# LabPower-FB_V2.net
KiCad netlist of a schematic drawn in EAGLE
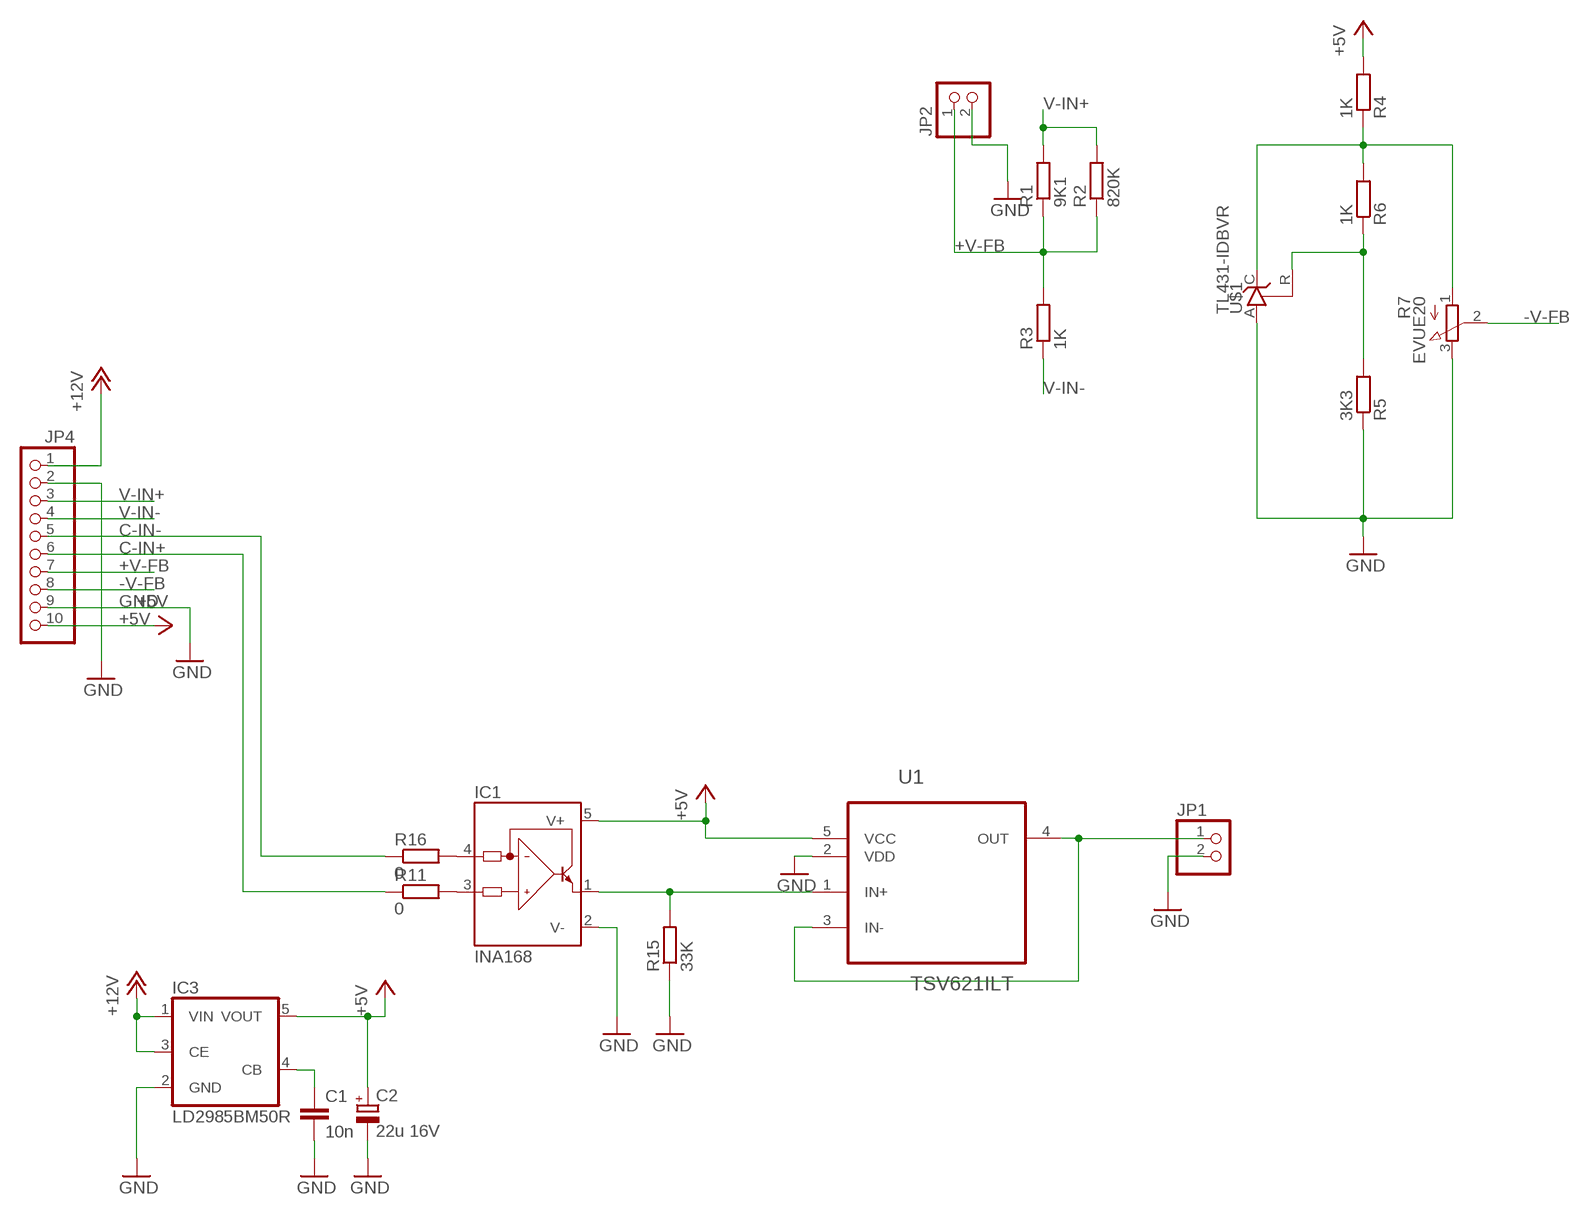
[diagram p0: schematic, sheet 1]

(export (version "E")
  (design (tool "Eeschema 10.0.6"))
  (components
    (comp (ref "C1")
      (value "10n")
      (footprint "eagle-import:C0805")
      (libsource (lib "eagle-import") (part "C-EUC0805"))
    )
    (comp (ref "C2")
      (value "22u 16V")
      (footprint "eagle-import:B_3528-21W")
      (libsource (lib "eagle-import") (part "CPOL-EUB/3528-21W"))
    )
    (comp (ref "IC1")
      (value "INA168")
      (footprint "eagle-import:SOT23-5")
      (fields (field (name "MF") "TEXAS INSTRUMENTS") (field (name "MPN") "INA168NA/250"))
      (libsource (lib "eagle-import") (part "INA168"))
    )
    (comp (ref "IC3")
      (value "LD2985BM50R")
      (footprint "eagle-import:SOT25")
      (libsource (lib "eagle-import") (part "TS5205"))
    )
    (comp (ref "JP1")
      (value "PINHD-1X2/90")
      (footprint "eagle-import:1X02_90")
      (libsource (lib "eagle-import") (part "PINHD-1X2/90"))
    )
    (comp (ref "JP2")
      (value "PINHD-1X2/90")
      (footprint "eagle-import:1X02_90")
      (libsource (lib "eagle-import") (part "PINHD-1X2/90"))
    )
    (comp (ref "JP4")
      (value "PINHD-1X10")
      (footprint "eagle-import:1X10")
      (libsource (lib "eagle-import") (part "PINHD-1X10"))
    )
    (comp (ref "R1")
      (value "9K1")
      (footprint "eagle-import:R0805")
      (libsource (lib "eagle-import") (part "R-EU_R0805"))
    )
    (comp (ref "R2")
      (value "820K")
      (footprint "eagle-import:R0805")
      (libsource (lib "eagle-import") (part "R-EU_R0805"))
    )
    (comp (ref "R3")
      (value "1K")
      (footprint "eagle-import:R0805")
      (libsource (lib "eagle-import") (part "R-EU_R0805"))
    )
    (comp (ref "R4")
      (value "1K")
      (footprint "eagle-import:R0805")
      (libsource (lib "eagle-import") (part "R-EU_R0805"))
    )
    (comp (ref "R5")
      (value "3K3")
      (footprint "eagle-import:R0805")
      (libsource (lib "eagle-import") (part "R-EU_R0805"))
    )
    (comp (ref "R6")
      (value "1K")
      (footprint "eagle-import:R0805")
      (libsource (lib "eagle-import") (part "R-EU_R0805"))
    )
    (comp (ref "R7")
      (value "EVUE20")
      (footprint "eagle-import:EVUE")
      (libsource (lib "eagle-import") (part "EVUE20"))
    )
    (comp (ref "R11")
      (value "0")
      (footprint "eagle-import:R0805")
      (libsource (lib "eagle-import") (part "R-EU_R0805"))
    )
    (comp (ref "R15")
      (value "33K")
      (footprint "eagle-import:R0805")
      (libsource (lib "eagle-import") (part "R-EU_R0805"))
    )
    (comp (ref "R16")
      (value "0")
      (footprint "eagle-import:R0805")
      (libsource (lib "eagle-import") (part "R-EU_R0805"))
    )
    (comp (ref "U$1")
      (value "TL431-IDBVR")
      (footprint "eagle-import:SOT23-5")
      (libsource (lib "eagle-import") (part "TL431-IDBVR"))
    )
    (comp (ref "U1")
      (value "TSV621ILT")
      (footprint "eagle-import:SOT95P280X145-5N")
      (libsource (lib "eagle-import") (part "TSV621ILT"))
    )
  )
  (nets
    (net (code "1") (name "+5V") (class "Default")
      (node (ref "C2") (pin "+") (pinfunction "+_+") (pintype "passive"))
      (node (ref "IC1") (pin "5") (pinfunction "V+_5") (pintype "power_in"))
      (node (ref "IC3") (pin "5") (pinfunction "VOUT_5") (pintype "passive"))
      (node (ref "JP4") (pin "10") (pinfunction "10_10") (pintype "passive"))
      (node (ref "R4") (pin "2") (pinfunction "2_2") (pintype "passive"))
      (node (ref "U1") (pin "5") (pinfunction "VCC_5") (pintype "power_in"))
    )
    (net (code "2") (name "+12V") (class "Default")
      (node (ref "IC3") (pin "1") (pinfunction "VIN_1") (pintype "input"))
      (node (ref "IC3") (pin "3") (pinfunction "CE_3") (pintype "input"))
      (node (ref "JP4") (pin "1") (pinfunction "1_1") (pintype "passive"))
    )
    (net (code "3") (name "/+V-FB") (class "Default")
      (node (ref "JP2") (pin "1") (pinfunction "1_1") (pintype "passive"))
      (node (ref "JP4") (pin "7") (pinfunction "7_7") (pintype "passive"))
      (node (ref "R1") (pin "1") (pinfunction "1_1") (pintype "passive"))
      (node (ref "R2") (pin "1") (pinfunction "1_1") (pintype "passive"))
      (node (ref "R3") (pin "2") (pinfunction "2_2") (pintype "passive"))
    )
    (net (code "4") (name "/-V-FB") (class "Default")
      (node (ref "JP4") (pin "8") (pinfunction "8_8") (pintype "passive"))
      (node (ref "R7") (pin "2") (pinfunction "S_2") (pintype "passive"))
    )
    (net (code "5") (name "/C-IN+") (class "Default")
      (node (ref "JP4") (pin "6") (pinfunction "6_6") (pintype "passive"))
      (node (ref "R11") (pin "1") (pinfunction "1_1") (pintype "passive"))
    )
    (net (code "6") (name "/C-IN-") (class "Default")
      (node (ref "JP4") (pin "5") (pinfunction "5_5") (pintype "passive"))
      (node (ref "R16") (pin "1") (pinfunction "1_1") (pintype "passive"))
    )
    (net (code "7") (name "/V-IN+") (class "Default")
      (node (ref "JP4") (pin "3") (pinfunction "3_3") (pintype "passive"))
      (node (ref "R1") (pin "2") (pinfunction "2_2") (pintype "passive"))
      (node (ref "R2") (pin "2") (pinfunction "2_2") (pintype "passive"))
    )
    (net (code "8") (name "/V-IN-") (class "Default")
      (node (ref "JP4") (pin "4") (pinfunction "4_4") (pintype "passive"))
      (node (ref "R3") (pin "1") (pinfunction "1_1") (pintype "passive"))
    )
    (net (code "9") (name "GND") (class "Default")
      (node (ref "C1") (pin "2") (pinfunction "2_2") (pintype "passive"))
      (node (ref "C2") (pin "-") (pinfunction "-_-") (pintype "passive"))
      (node (ref "IC1") (pin "2") (pinfunction "V-_2") (pintype "power_in"))
      (node (ref "IC3") (pin "2") (pinfunction "GND_2") (pintype "passive"))
      (node (ref "JP1") (pin "2") (pinfunction "2_2") (pintype "passive"))
      (node (ref "JP2") (pin "2") (pinfunction "2_2") (pintype "passive"))
      (node (ref "JP4") (pin "2") (pinfunction "2_2") (pintype "passive"))
      (node (ref "JP4") (pin "9") (pinfunction "9_9") (pintype "passive"))
      (node (ref "R15") (pin "1") (pinfunction "1_1") (pintype "passive"))
      (node (ref "R5") (pin "1") (pinfunction "1_1") (pintype "passive"))
      (node (ref "R7") (pin "3") (pinfunction "E_3") (pintype "passive"))
      (node (ref "U$1") (pin "A") (pinfunction "A_A") (pintype "passive"))
      (node (ref "U1") (pin "2") (pinfunction "VDD_2") (pintype "power_in"))
    )
    (net (code "10") (name "Net-(IC1-IN+)") (class "Default")
      (node (ref "IC1") (pin "3") (pinfunction "IN+_3") (pintype "input"))
      (node (ref "R11") (pin "2") (pinfunction "2_2") (pintype "passive"))
    )
    (net (code "11") (name "Net-(IC1-IN-)") (class "Default")
      (node (ref "IC1") (pin "4") (pinfunction "IN-_4") (pintype "input"))
      (node (ref "R16") (pin "2") (pinfunction "2_2") (pintype "passive"))
    )
    (net (code "12") (name "Net-(IC1-OUT)") (class "Default")
      (node (ref "IC1") (pin "1") (pinfunction "OUT_1") (pintype "output"))
      (node (ref "R15") (pin "2") (pinfunction "2_2") (pintype "passive"))
      (node (ref "U1") (pin "1") (pinfunction "IN+_1") (pintype "input"))
    )
    (net (code "13") (name "Net-(IC3-CB)") (class "Default")
      (node (ref "C1") (pin "1") (pinfunction "1_1") (pintype "passive"))
      (node (ref "IC3") (pin "4") (pinfunction "CB_4") (pintype "input"))
    )
    (net (code "14") (name "Net-(R5-Pad2)") (class "Default")
      (node (ref "R5") (pin "2") (pinfunction "2_2") (pintype "passive"))
      (node (ref "R6") (pin "1") (pinfunction "1_1") (pintype "passive"))
      (node (ref "U$1") (pin "R") (pinfunction "R_R") (pintype "passive"))
    )
    (net (code "15") (name "Net-(R7-A)") (class "Default")
      (node (ref "R4") (pin "1") (pinfunction "1_1") (pintype "passive"))
      (node (ref "R6") (pin "2") (pinfunction "2_2") (pintype "passive"))
      (node (ref "R7") (pin "1") (pinfunction "A_1") (pintype "passive"))
      (node (ref "U$1") (pin "C") (pinfunction "C_C") (pintype "passive"))
    )
    (net (code "16") (name "Net-(U1-IN-)") (class "Default")
      (node (ref "JP1") (pin "1") (pinfunction "1_1") (pintype "passive"))
      (node (ref "U1") (pin "3") (pinfunction "IN-_3") (pintype "input"))
      (node (ref "U1") (pin "4") (pinfunction "OUT_4") (pintype "output"))
    )
  )
)
